# VoltageRegulator1.net
KiCad netlist of a schematic drawn in Altium Designer
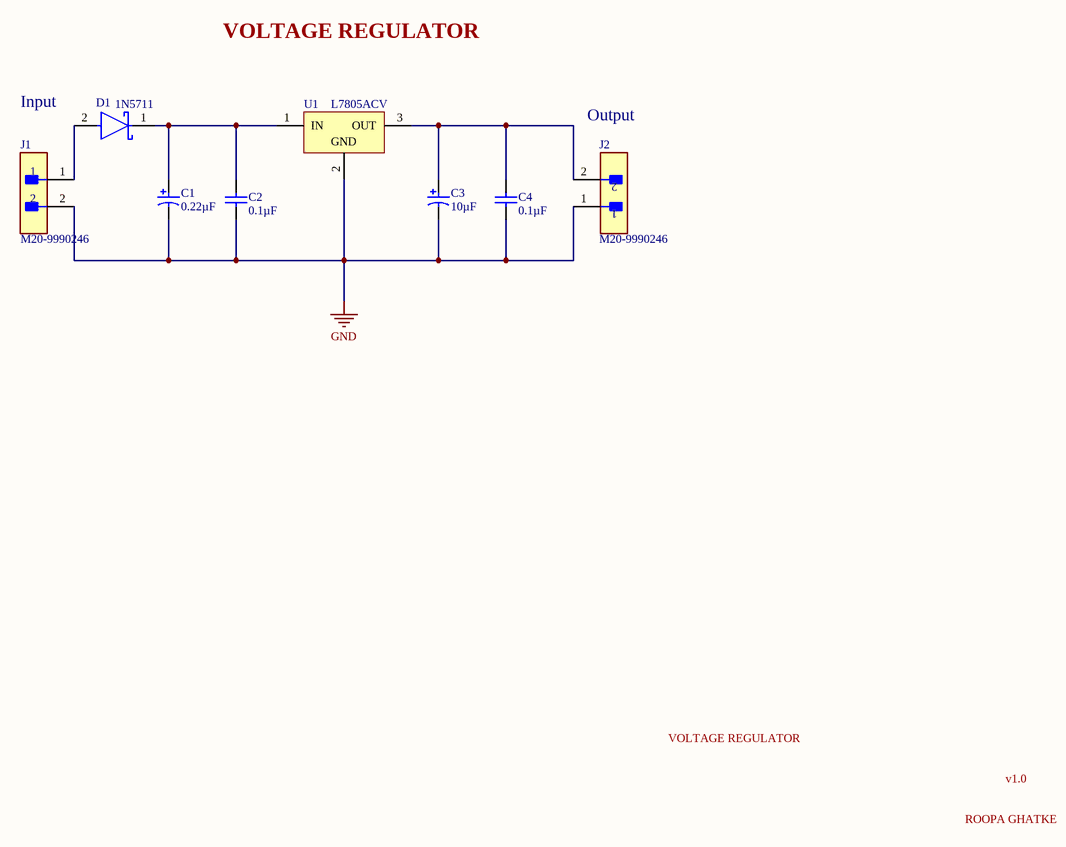
[diagram p0: VoltageRegulator1.SchDoc]

(export (version "E")
  (design (tool "Eeschema 10.0.6"))
  (components
    (comp (ref "C1")
      (value "0.22µF")
      (footprint "CAPPR55-200-1100X500X1200")
      (description "Aluminum Electrolytic Capacitor, 2.2 uF, +/- 20%, 50 V, -40 to 85 degC, 2-Pin THD, RoHS, Bulk")
      (fields (field (name "VOLTAGE") "50V") (field (name "MANUFACTURER") "Panasonic"))
      (libsource (lib "Altium Content Vault") (part "CAP-P-2"))
    )
    (comp (ref "C2")
      (value "0.1µF")
      (footprint "CAPR51-254-508X318X736")
      (libsource (lib "Altium Content Vault") (part "CAP-NP-2"))
    )
    (comp (ref "C3")
      (value "10µF")
      (footprint "CAPPR55-200-1100X500X1200")
      (description "Aluminum Electrolytic Capacitor, 22 uF, +/- 20%, 50 V, -40 to 85 degC, 2-Pin THD, RoHS, Bulk")
      (fields (field (name "VOLTAGE") "50V") (field (name "MANUFACTURER") "Panasonic"))
      (libsource (lib "Altium Content Vault") (part "CAP-P-2"))
    )
    (comp (ref "C4")
      (value "0.1µF")
      (footprint "CAPR51-254-508X318X736")
      (libsource (lib "Altium Content Vault") (part "CAP-NP-2"))
    )
    (comp (ref "D1")
      (value "1N5711")
      (footprint "FP-DO-35-MFG")
      (description "RF DIODE SCHOTTKY 70V 430MW DO35")
      (fields
        (field (name "MANUFACTURER") "STMicroelectronics")
        (field (name "OCTOPART") "https://octopart.com/1n5711-stmicroelectronics-55399277")
      )
      (libsource (lib "Altium Content Vault") (part "1d6ec82d83fb6aee721767c19dac4b9"))
    )
    (comp (ref "J1")
      (value "M20-9990246")
      (footprint "FP-M20-9990246-MFG")
      (description "CONN HEADER VERT 2POS 2.54MM")
      (fields
        (field (name "OCTOPART") "https://octopart.com/m20-9990246-harwin-2590635")
        (field (name "MANUFACTURER") "Harwin")
      )
      (libsource (lib "") (part "3bc925449376181038e59eaffc5286c_1"))
    )
    (comp (ref "J2")
      (value "M20-9990246")
      (footprint "FP-M20-9990246-MFG")
      (description "CONN HEADER VERT 2POS 2.54MM")
      (fields
        (field (name "OCTOPART") "https://octopart.com/m20-9990246-harwin-2590635")
        (field (name "MANUFACTURER") "Harwin")
      )
      (libsource (lib "Altium Content Vault") (part "3bc925449376181038e59eaffc5286c"))
    )
    (comp (ref "U1")
      (value "L7805ACV")
      (footprint "TO220")
      (description "Positive Voltage Regulator, 5V, 3-Pin TO-220")
      (libsource (lib "Altium Content Vault") (part "PM-REG-L4940-SIL3"))
    )
  )
  (nets
    (net (code "2") (name "GND") (class "Default")
      (node (ref "C1") (pin "2") (pinfunction "2_2") (pintype "passive"))
      (node (ref "C2") (pin "2") (pinfunction "2_2") (pintype "passive"))
      (node (ref "C3") (pin "2") (pinfunction "2_2") (pintype "passive"))
      (node (ref "C4") (pin "1") (pinfunction "1_1") (pintype "passive"))
      (node (ref "J1") (pin "2") (pinfunction "2_2") (pintype "passive"))
      (node (ref "J2") (pin "1") (pinfunction "1_1") (pintype "passive"))
      (node (ref "U1") (pin "2") (pinfunction "GND_2") (pintype "power_in"))
    )
    (net (code "3") (name "Net-(D1-A)") (class "Default")
      (node (ref "D1") (pin "2") (pinfunction "A_2") (pintype "passive"))
      (node (ref "J1") (pin "1") (pinfunction "1_1") (pintype "passive"))
    )
    (net (code "4") (name "Net-(D1-C)") (class "Default")
      (node (ref "C1") (pin "1") (pinfunction "1_1") (pintype "passive"))
      (node (ref "C2") (pin "1") (pinfunction "1_1") (pintype "passive"))
      (node (ref "D1") (pin "1") (pinfunction "C_1") (pintype "passive"))
      (node (ref "U1") (pin "1") (pinfunction "IN_1") (pintype "power_in"))
    )
    (net (code "5") (name "Net-(U1-OUT)") (class "Default")
      (node (ref "C3") (pin "1") (pinfunction "1_1") (pintype "passive"))
      (node (ref "C4") (pin "2") (pinfunction "2_2") (pintype "passive"))
      (node (ref "J2") (pin "2") (pinfunction "2_2") (pintype "passive"))
      (node (ref "U1") (pin "3") (pinfunction "OUT_3") (pintype "power_in"))
    )
  )
)
